# LM2825_schematic.net
KiCad netlist of a schematic drawn in EAGLE
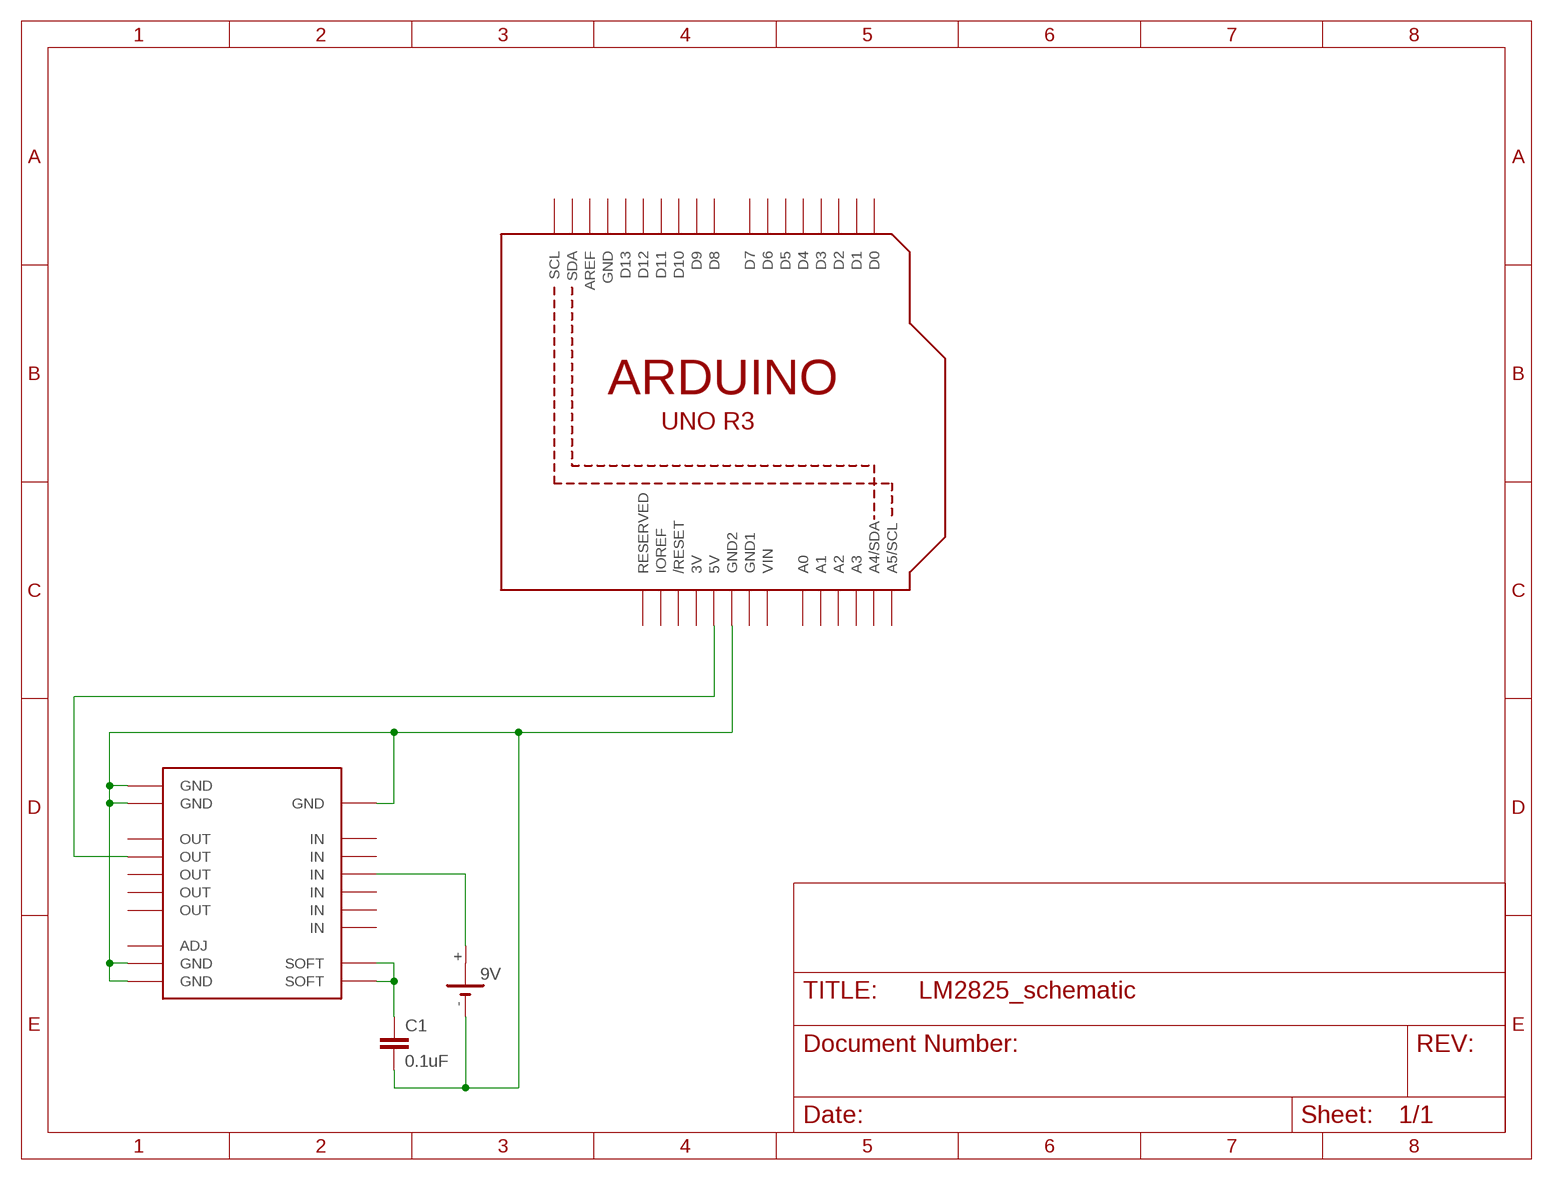
[diagram p0: schematic, sheet 1]

(export (version "E")
  (design (tool "Eeschema 10.0.6"))
  (components
    (comp (ref "9V")
      (value "1V60R")
      (footprint "eagle-import:1V60R")
      (libsource (lib "eagle-import") (part "1V60R"))
    )
    (comp (ref "C1")
      (value "0.1uF")
      (footprint "eagle-import:XC10B5")
      (libsource (lib "eagle-import") (part "CXXC10B5"))
    )
    (comp (ref "U$5")
      (value "TI_LM2825")
      (footprint "eagle-import:TI_LM2825_HEADERS")
      (libsource (lib "eagle-import") (part "TI_LM2825"))
    )
    (comp (ref "U1")
      (value "ARDUINOR3-DIMENSION")
      (footprint "eagle-import:ARDUINOR3")
      (libsource (lib "eagle-import") (part "ARDUINOR3-DIMENSION"))
    )
  )
  (nets
    (net (code "1") (name "/3V") (class "Default")
      (node (ref "U1") (pin "3V") (pinfunction "3V_3V") (pintype "power_in"))
    )
    (net (code "2") (name "/GND") (class "Default")
      (node (ref "U1") (pin "GND") (pinfunction "GND_GND") (pintype "power_in"))
    )
    (net (code "3") (name "/GND1") (class "Default")
      (node (ref "U1") (pin "GND1") (pinfunction "GND1_GND1") (pintype "power_in"))
    )
    (net (code "4") (name "/VIN") (class "Default")
      (node (ref "U1") (pin "VIN") (pinfunction "VIN_VIN") (pintype "power_in"))
    )
    (net (code "5") (name "Net-(9V-Pad+)") (class "Default")
      (node (ref "9V") (pin "+") (pinfunction "+_+") (pintype "passive"))
      (node (ref "U$5") (pin "IN@19") (pinfunction "IN_IN@19") (pintype "input"))
    )
    (net (code "6") (name "Net-(9V-Pad-)") (class "Default")
      (node (ref "9V") (pin "-") (pinfunction "-_-") (pintype "passive"))
      (node (ref "C1") (pin "2") (pinfunction "2_2") (pintype "passive"))
      (node (ref "U$5") (pin "GND@1") (pinfunction "GND_GND@1") (pintype "power_in"))
      (node (ref "U$5") (pin "GND@11") (pinfunction "GND_GND@11") (pintype "power_in"))
      (node (ref "U$5") (pin "GND@12") (pinfunction "GND_GND@12") (pintype "power_in"))
      (node (ref "U$5") (pin "GND@2") (pinfunction "GND_GND@2") (pintype "power_in"))
      (node (ref "U$5") (pin "GND@23") (pinfunction "GND_GND@23") (pintype "power_in"))
      (node (ref "U1") (pin "GND2") (pinfunction "GND2_GND2") (pintype "power_in"))
    )
    (net (code "7") (name "Net-(C1-Pad1)") (class "Default")
      (node (ref "C1") (pin "1") (pinfunction "1_1") (pintype "passive"))
      (node (ref "U$5") (pin "SOFT@13") (pinfunction "SOFT_SOFT@13") (pintype "passive"))
      (node (ref "U$5") (pin "SOFT@14") (pinfunction "SOFT_SOFT@14") (pintype "passive"))
    )
    (net (code "8") (name "Net-(U$5-OUT-PadOUT@5)") (class "Default")
      (node (ref "U$5") (pin "OUT@5") (pinfunction "OUT_OUT@5") (pintype "output"))
      (node (ref "U1") (pin "5V") (pinfunction "5V_5V") (pintype "power_in"))
    )
    (net (code "9") (name "unconnected-(9V-+-Pad+@1)") (class "Default")
      (node (ref "9V") (pin "+@1") (pinfunction "+_+@1") (pintype "passive"))
    )
    (net (code "10") (name "unconnected-(U$5-IN-PadIN@16)") (class "Default")
      (node (ref "U$5") (pin "IN@16") (pinfunction "IN_IN@16") (pintype "input"))
    )
    (net (code "11") (name "unconnected-(U$5-IN-PadIN@17)") (class "Default")
      (node (ref "U$5") (pin "IN@17") (pinfunction "IN_IN@17") (pintype "input"))
    )
    (net (code "12") (name "unconnected-(U$5-IN-PadIN@18)") (class "Default")
      (node (ref "U$5") (pin "IN@18") (pinfunction "IN_IN@18") (pintype "input"))
    )
    (net (code "13") (name "unconnected-(U$5-IN-PadIN@20)") (class "Default")
      (node (ref "U$5") (pin "IN@20") (pinfunction "IN_IN@20") (pintype "input"))
    )
    (net (code "14") (name "unconnected-(U$5-IN-PadIN@21)") (class "Default")
      (node (ref "U$5") (pin "IN@21") (pinfunction "IN_IN@21") (pintype "input"))
    )
    (net (code "15") (name "unconnected-(U$5-OUT-PadOUT@4)") (class "Default")
      (node (ref "U$5") (pin "OUT@4") (pinfunction "OUT_OUT@4") (pintype "output"))
    )
    (net (code "16") (name "unconnected-(U$5-OUT-PadOUT@6)") (class "Default")
      (node (ref "U$5") (pin "OUT@6") (pinfunction "OUT_OUT@6") (pintype "output"))
    )
    (net (code "17") (name "unconnected-(U$5-OUT-PadOUT@7)") (class "Default")
      (node (ref "U$5") (pin "OUT@7") (pinfunction "OUT_OUT@7") (pintype "output"))
    )
    (net (code "18") (name "unconnected-(U$5-OUT-PadOUT@8)") (class "Default")
      (node (ref "U$5") (pin "OUT@8") (pinfunction "OUT_OUT@8") (pintype "output"))
    )
    (net (code "19") (name "unconnected-(U$5-PadADJ)") (class "Default")
      (node (ref "U$5") (pin "ADJ") (pinfunction "ADJ_ADJ") (pintype "passive"))
    )
    (net (code "20") (name "unconnected-(U1-A4{slash}SDA-PadA4)") (class "Default")
      (node (ref "U1") (pin "A4") (pinfunction "A4/SDA_A4") (pintype "bidirectional"))
    )
    (net (code "21") (name "unconnected-(U1-A5{slash}SCL-PadA5)") (class "Default")
      (node (ref "U1") (pin "A5") (pinfunction "A5/SCL_A5") (pintype "bidirectional"))
    )
    (net (code "22") (name "unconnected-(U1-PadA0)") (class "Default")
      (node (ref "U1") (pin "A0") (pinfunction "A0_A0") (pintype "bidirectional"))
    )
    (net (code "23") (name "unconnected-(U1-PadA1)") (class "Default")
      (node (ref "U1") (pin "A1") (pinfunction "A1_A1") (pintype "bidirectional"))
    )
    (net (code "24") (name "unconnected-(U1-PadA2)") (class "Default")
      (node (ref "U1") (pin "A2") (pinfunction "A2_A2") (pintype "bidirectional"))
    )
    (net (code "25") (name "unconnected-(U1-PadA3)") (class "Default")
      (node (ref "U1") (pin "A3") (pinfunction "A3_A3") (pintype "bidirectional"))
    )
    (net (code "26") (name "unconnected-(U1-PadAREF)") (class "Default")
      (node (ref "U1") (pin "AREF") (pinfunction "AREF_AREF") (pintype "bidirectional"))
    )
    (net (code "27") (name "unconnected-(U1-PadD0)") (class "Default")
      (node (ref "U1") (pin "D0") (pinfunction "D0_D0") (pintype "bidirectional"))
    )
    (net (code "28") (name "unconnected-(U1-PadD1)") (class "Default")
      (node (ref "U1") (pin "D1") (pinfunction "D1_D1") (pintype "bidirectional"))
    )
    (net (code "29") (name "unconnected-(U1-PadD2)") (class "Default")
      (node (ref "U1") (pin "D2") (pinfunction "D2_D2") (pintype "bidirectional"))
    )
    (net (code "30") (name "unconnected-(U1-PadD3)") (class "Default")
      (node (ref "U1") (pin "D3") (pinfunction "D3_D3") (pintype "bidirectional"))
    )
    (net (code "31") (name "unconnected-(U1-PadD4)") (class "Default")
      (node (ref "U1") (pin "D4") (pinfunction "D4_D4") (pintype "bidirectional"))
    )
    (net (code "32") (name "unconnected-(U1-PadD5)") (class "Default")
      (node (ref "U1") (pin "D5") (pinfunction "D5_D5") (pintype "bidirectional"))
    )
    (net (code "33") (name "unconnected-(U1-PadD6)") (class "Default")
      (node (ref "U1") (pin "D6") (pinfunction "D6_D6") (pintype "bidirectional"))
    )
    (net (code "34") (name "unconnected-(U1-PadD7)") (class "Default")
      (node (ref "U1") (pin "D7") (pinfunction "D7_D7") (pintype "bidirectional"))
    )
    (net (code "35") (name "unconnected-(U1-PadD8)") (class "Default")
      (node (ref "U1") (pin "D8") (pinfunction "D8_D8") (pintype "bidirectional"))
    )
    (net (code "36") (name "unconnected-(U1-PadD9)") (class "Default")
      (node (ref "U1") (pin "D9") (pinfunction "D9_D9") (pintype "bidirectional"))
    )
    (net (code "37") (name "unconnected-(U1-PadD10)") (class "Default")
      (node (ref "U1") (pin "D10") (pinfunction "D10_D10") (pintype "bidirectional"))
    )
    (net (code "38") (name "unconnected-(U1-PadD11)") (class "Default")
      (node (ref "U1") (pin "D11") (pinfunction "D11_D11") (pintype "bidirectional"))
    )
    (net (code "39") (name "unconnected-(U1-PadD12)") (class "Default")
      (node (ref "U1") (pin "D12") (pinfunction "D12_D12") (pintype "bidirectional"))
    )
    (net (code "40") (name "unconnected-(U1-PadD13)") (class "Default")
      (node (ref "U1") (pin "D13") (pinfunction "D13_D13") (pintype "bidirectional"))
    )
    (net (code "41") (name "unconnected-(U1-PadIOREF)") (class "Default")
      (node (ref "U1") (pin "IOREF") (pinfunction "IOREF_IOREF") (pintype "output"))
    )
    (net (code "42") (name "unconnected-(U1-PadRESERVED)") (class "Default")
      (node (ref "U1") (pin "RESERVED") (pinfunction "RESERVED_RESERVED") (pintype "no_connect"))
    )
    (net (code "43") (name "unconnected-(U1-PadSCL)") (class "Default")
      (node (ref "U1") (pin "SCL") (pinfunction "SCL_SCL") (pintype "bidirectional"))
    )
    (net (code "44") (name "unconnected-(U1-PadSDA)") (class "Default")
      (node (ref "U1") (pin "SDA") (pinfunction "SDA_SDA") (pintype "bidirectional"))
    )
    (net (code "45") (name "unconnected-(U1-{slash}RESET-PadRESET)") (class "Default")
      (node (ref "U1") (pin "RESET") (pinfunction "/RESET_RESET") (pintype "bidirectional"))
    )
  )
)
